# Sp_OLED_BUTTOMS.net
KiCad netlist of a schematic drawn in EAGLE
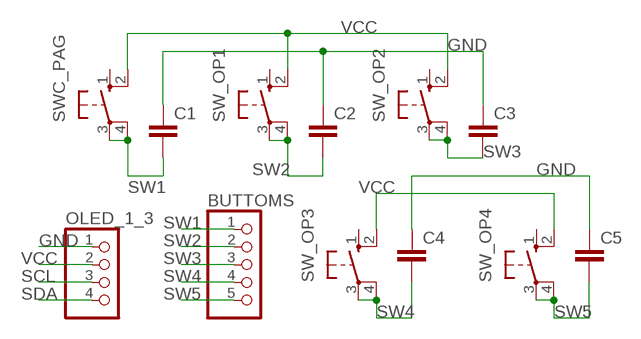
[diagram p0: schematic, sheet 1]

(export (version "E")
  (design (tool "Eeschema 10.0.6"))
  (components
    (comp (ref "BUTTOMS")
      (value "PINHD-1X5")
      (footprint "eagle-import:1X05")
      (libsource (lib "eagle-import") (part "PINHD-1X5"))
    )
    (comp (ref "C1")
      (value "C2,5-3")
      (footprint "eagle-import:C2.5-3")
      (libsource (lib "eagle-import") (part "C2,5-3"))
    )
    (comp (ref "C2")
      (value "C2,5-3")
      (footprint "eagle-import:C2.5-3")
      (libsource (lib "eagle-import") (part "C2,5-3"))
    )
    (comp (ref "C3")
      (value "C2,5-3")
      (footprint "eagle-import:C2.5-3")
      (libsource (lib "eagle-import") (part "C2,5-3"))
    )
    (comp (ref "C4")
      (value "C2,5-3")
      (footprint "eagle-import:C2.5-3")
      (libsource (lib "eagle-import") (part "C2,5-3"))
    )
    (comp (ref "C5")
      (value "C2,5-3")
      (footprint "eagle-import:C2.5-3")
      (libsource (lib "eagle-import") (part "C2,5-3"))
    )
    (comp (ref "OLED_1_3")
      (value "PINHD-1X4")
      (footprint "eagle-import:1X04")
      (libsource (lib "eagle-import") (part "PINHD-1X4"))
    )
    (comp (ref "SWC_PAG")
      (value "10-XX")
      (footprint "eagle-import:B3F-10XX")
      (fields (field (name "MPN") "B3F-1000"))
      (libsource (lib "eagle-import") (part "10-XX"))
    )
    (comp (ref "SW_OP1")
      (value "10-XX")
      (footprint "eagle-import:B3F-10XX")
      (fields (field (name "MPN") "B3F-1000"))
      (libsource (lib "eagle-import") (part "10-XX"))
    )
    (comp (ref "SW_OP2")
      (value "10-XX")
      (footprint "eagle-import:B3F-10XX")
      (fields (field (name "MPN") "B3F-1000"))
      (libsource (lib "eagle-import") (part "10-XX"))
    )
    (comp (ref "SW_OP3")
      (value "10-XX")
      (footprint "eagle-import:B3F-10XX")
      (fields (field (name "MPN") "B3F-1000"))
      (libsource (lib "eagle-import") (part "10-XX"))
    )
    (comp (ref "SW_OP4")
      (value "10-XX")
      (footprint "eagle-import:B3F-10XX")
      (fields (field (name "MPN") "B3F-1000"))
      (libsource (lib "eagle-import") (part "10-XX"))
    )
  )
  (nets
    (net (code "1") (name "/GND") (class "Default")
      (node (ref "C1") (pin "1") (pinfunction "1_1") (pintype "passive"))
      (node (ref "C2") (pin "1") (pinfunction "1_1") (pintype "passive"))
      (node (ref "C3") (pin "1") (pinfunction "1_1") (pintype "passive"))
      (node (ref "C4") (pin "1") (pinfunction "1_1") (pintype "passive"))
      (node (ref "C5") (pin "1") (pinfunction "1_1") (pintype "passive"))
      (node (ref "OLED_1_3") (pin "1") (pinfunction "1_1") (pintype "passive"))
    )
    (net (code "2") (name "/SCL") (class "Default")
      (node (ref "OLED_1_3") (pin "3") (pinfunction "3_3") (pintype "passive"))
    )
    (net (code "3") (name "/SDA") (class "Default")
      (node (ref "OLED_1_3") (pin "4") (pinfunction "4_4") (pintype "passive"))
    )
    (net (code "4") (name "/SW1") (class "Default")
      (node (ref "BUTTOMS") (pin "1") (pinfunction "1_1") (pintype "passive"))
      (node (ref "C1") (pin "2") (pinfunction "2_2") (pintype "passive"))
      (node (ref "SWC_PAG") (pin "3") (pinfunction "P_3") (pintype "passive"))
      (node (ref "SWC_PAG") (pin "4") (pinfunction "P1_4") (pintype "passive"))
    )
    (net (code "5") (name "/SW2") (class "Default")
      (node (ref "BUTTOMS") (pin "2") (pinfunction "2_2") (pintype "passive"))
      (node (ref "C2") (pin "2") (pinfunction "2_2") (pintype "passive"))
      (node (ref "SW_OP1") (pin "3") (pinfunction "P_3") (pintype "passive"))
      (node (ref "SW_OP1") (pin "4") (pinfunction "P1_4") (pintype "passive"))
    )
    (net (code "6") (name "/SW3") (class "Default")
      (node (ref "BUTTOMS") (pin "3") (pinfunction "3_3") (pintype "passive"))
      (node (ref "C3") (pin "2") (pinfunction "2_2") (pintype "passive"))
      (node (ref "SW_OP2") (pin "3") (pinfunction "P_3") (pintype "passive"))
      (node (ref "SW_OP2") (pin "4") (pinfunction "P1_4") (pintype "passive"))
    )
    (net (code "7") (name "/SW4") (class "Default")
      (node (ref "BUTTOMS") (pin "4") (pinfunction "4_4") (pintype "passive"))
      (node (ref "C4") (pin "2") (pinfunction "2_2") (pintype "passive"))
      (node (ref "SW_OP3") (pin "3") (pinfunction "P_3") (pintype "passive"))
      (node (ref "SW_OP3") (pin "4") (pinfunction "P1_4") (pintype "passive"))
    )
    (net (code "8") (name "/SW5") (class "Default")
      (node (ref "BUTTOMS") (pin "5") (pinfunction "5_5") (pintype "passive"))
      (node (ref "C5") (pin "2") (pinfunction "2_2") (pintype "passive"))
      (node (ref "SW_OP4") (pin "3") (pinfunction "P_3") (pintype "passive"))
      (node (ref "SW_OP4") (pin "4") (pinfunction "P1_4") (pintype "passive"))
    )
    (net (code "9") (name "/VCC") (class "Default")
      (node (ref "OLED_1_3") (pin "2") (pinfunction "2_2") (pintype "passive"))
      (node (ref "SWC_PAG") (pin "2") (pinfunction "S1_2") (pintype "passive"))
      (node (ref "SW_OP1") (pin "2") (pinfunction "S1_2") (pintype "passive"))
      (node (ref "SW_OP2") (pin "2") (pinfunction "S1_2") (pintype "passive"))
      (node (ref "SW_OP3") (pin "2") (pinfunction "S1_2") (pintype "passive"))
      (node (ref "SW_OP4") (pin "2") (pinfunction "S1_2") (pintype "passive"))
    )
    (net (code "10") (name "unconnected-(SWC_PAG-S-Pad1)") (class "Default")
      (node (ref "SWC_PAG") (pin "1") (pinfunction "S_1") (pintype "passive"))
    )
    (net (code "11") (name "unconnected-(SW_OP1-S-Pad1)") (class "Default")
      (node (ref "SW_OP1") (pin "1") (pinfunction "S_1") (pintype "passive"))
    )
    (net (code "12") (name "unconnected-(SW_OP2-S-Pad1)") (class "Default")
      (node (ref "SW_OP2") (pin "1") (pinfunction "S_1") (pintype "passive"))
    )
    (net (code "13") (name "unconnected-(SW_OP3-S-Pad1)") (class "Default")
      (node (ref "SW_OP3") (pin "1") (pinfunction "S_1") (pintype "passive"))
    )
    (net (code "14") (name "unconnected-(SW_OP4-S-Pad1)") (class "Default")
      (node (ref "SW_OP4") (pin "1") (pinfunction "S_1") (pintype "passive"))
    )
  )
)
